# CONNECTORS.net
KiCad netlist of a schematic drawn in Altium Designer
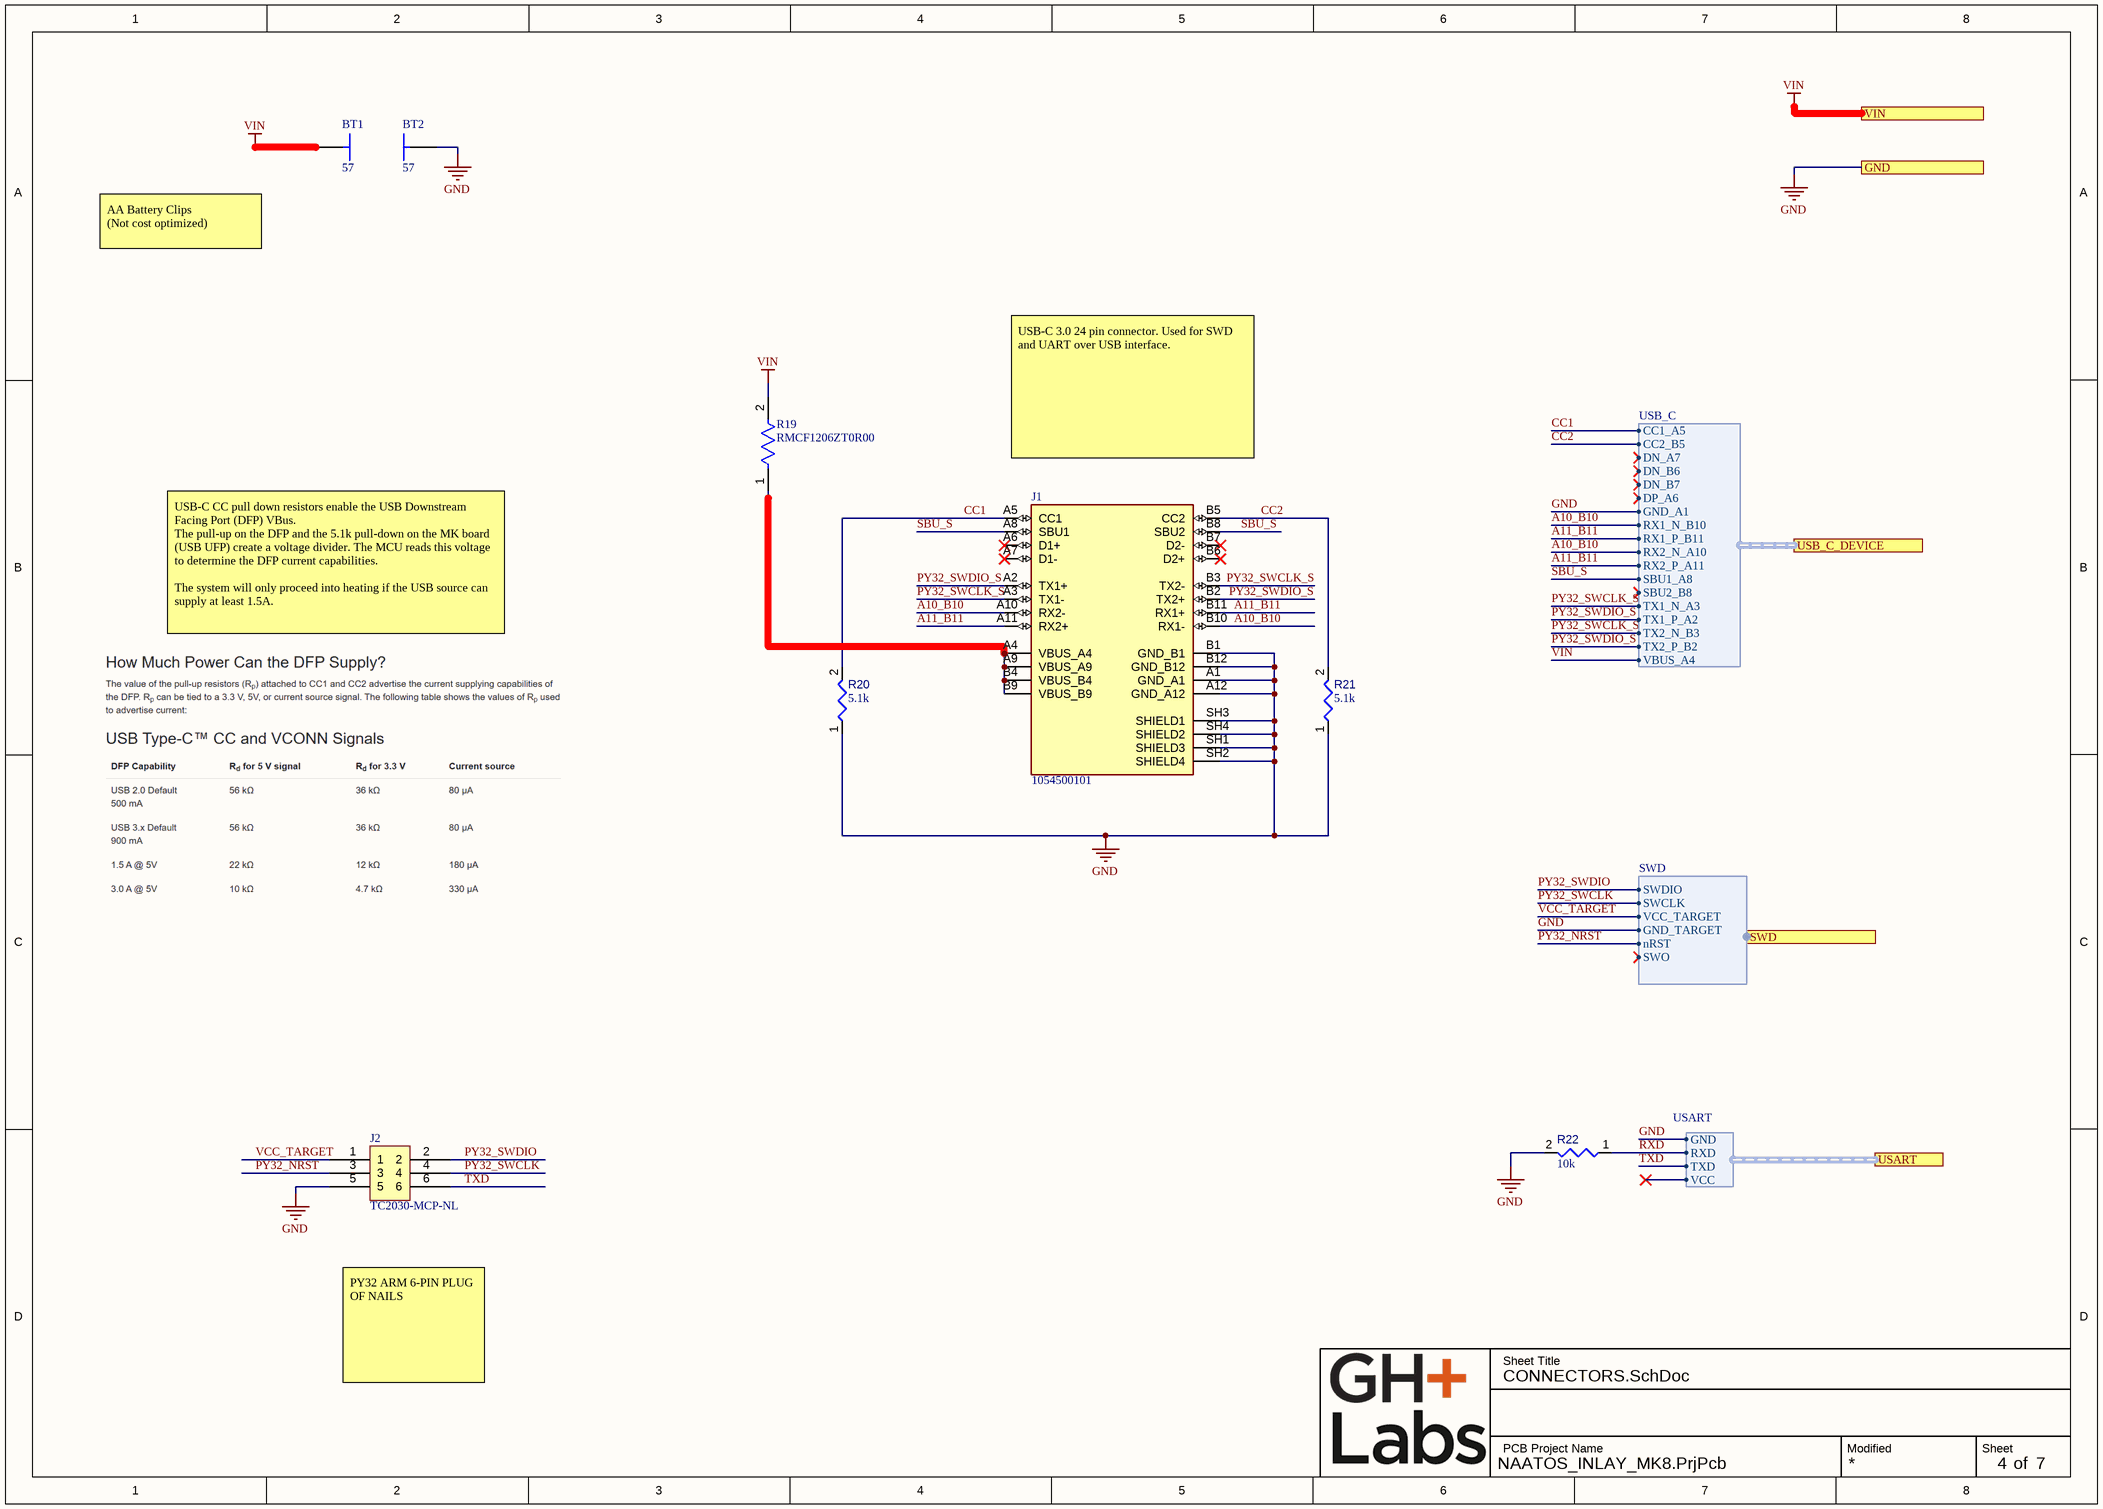
[diagram p0: CONNECTORS.SchDoc]

(export (version "E")
  (design (tool "Eeschema 10.0.6"))
  (components
    (comp (ref "BT1")
      (value "57")
      (footprint "57-Footprint-1")
      (description "A /AA SMT BATTERY CONTACT")
      (fields (field (name "MF") "Keystone Electronics"))
      (libsource (lib "Global Health Labs, Inc") (part "BT1"))
    )
    (comp (ref "BT2")
      (value "57")
      (footprint "57-Footprint-1")
      (description "A /AA SMT BATTERY CONTACT")
      (fields (field (name "MF") "Keystone Electronics"))
      (libsource (lib "Global Health Labs, Inc") (part "BT1"))
    )
    (comp (ref "J1")
      (value "1054500101")
      (footprint "MOLEX_1054500101")
      (fields (field (name "MF") "Molex"))
      (libsource (lib "Global Health Labs, Inc") (part "1054500101"))
    )
    (comp (ref "J2")
      (value "TC2030-MCP-NL")
      (footprint "TC2030-MCP-NL")
      (description "TAG CONNECT FOR UPDI")
      (libsource (lib "TC2030-MCP-NL") (part "TC2030-MCP-NL"))
    )
    (comp (ref "R19")
      (value "RMCF1206ZT0R00")
      (footprint "FP-RMCF1206-MFG")
      (description "0Ω ±0 0.25W 1206 Thick Film Chip Resistor AEC-Q200 compliant")
      (libsource (lib "Altium Content Vault") (part "1029c3af85768c4190bb7ad29bc67b5"))
    )
    (comp (ref "R20")
      (value "5.1k")
      (footprint "RESC0402(1005)_L")
      (description "Chip Resistor, 5.1 kOhms, +/-1 %, 63 mW, -55 to 155 degC, 0402")
      (fields (field (name "POWER") "63mW") (field (name "TOLERANCE") "1%"))
      (libsource (lib "Global Health Labs, Inc") (part "RES-2"))
    )
    (comp (ref "R21")
      (value "5.1k")
      (footprint "RESC0402(1005)_L")
      (description "Chip Resistor, 5.1 kOhms, +/-1 %, 63 mW, -55 to 155 degC, 0402")
      (fields (field (name "POWER") "63mW") (field (name "TOLERANCE") "1%"))
      (libsource (lib "Global Health Labs, Inc") (part "RES-2"))
    )
    (comp (ref "R22")
      (value "10k")
      (footprint "RESC0402(1005)_L")
      (description "Chip Resistor, 10 kOhms, +/-1 %, 63 mW, -55 to 125 degC, 0402")
      (fields (field (name "POWER") "63mW") (field (name "TOLERANCE") "1%"))
      (libsource (lib "Global Health Labs, Inc") (part "RES-2"))
    )
  )
  (nets
    (net (code "4") (name "/A10_B10") (class "Default")
      (node (ref "J1") (pin "A10") (pinfunction "RX2-_A10") (pintype "bidirectional"))
      (node (ref "J1") (pin "B10") (pinfunction "RX1-_B10") (pintype "bidirectional"))
    )
    (net (code "5") (name "/A11_B11") (class "Default")
      (node (ref "J1") (pin "A11") (pinfunction "RX2+_A11") (pintype "bidirectional"))
      (node (ref "J1") (pin "B11") (pinfunction "RX1+_B11") (pintype "bidirectional"))
    )
    (net (code "6") (name "/CC1") (class "Default")
      (node (ref "J1") (pin "A5") (pinfunction "CC1_A5") (pintype "bidirectional"))
      (node (ref "R20") (pin "2") (pinfunction "2_2") (pintype "passive"))
    )
    (net (code "7") (name "/CC2") (class "Default")
      (node (ref "J1") (pin "B5") (pinfunction "CC2_B5") (pintype "bidirectional"))
      (node (ref "R21") (pin "2") (pinfunction "2_2") (pintype "passive"))
    )
    (net (code "8") (name "/PY32_NRST") (class "Default")
      (node (ref "J2") (pin "3") (pinfunction "3_3") (pintype "passive"))
    )
    (net (code "9") (name "/PY32_SWCLK") (class "Default")
      (node (ref "J2") (pin "4") (pinfunction "4_4") (pintype "passive"))
    )
    (net (code "10") (name "/PY32_SWCLK_S") (class "Default")
      (node (ref "J1") (pin "A3") (pinfunction "TX1-_A3") (pintype "bidirectional"))
      (node (ref "J1") (pin "B3") (pinfunction "TX2-_B3") (pintype "bidirectional"))
    )
    (net (code "11") (name "/PY32_SWDIO") (class "Default")
      (node (ref "J2") (pin "2") (pinfunction "2_2") (pintype "passive"))
    )
    (net (code "12") (name "/PY32_SWDIO_S") (class "Default")
      (node (ref "J1") (pin "A2") (pinfunction "TX1+_A2") (pintype "bidirectional"))
      (node (ref "J1") (pin "B2") (pinfunction "TX2+_B2") (pintype "bidirectional"))
    )
    (net (code "13") (name "/RXD") (class "Default")
      (node (ref "R22") (pin "1") (pinfunction "1_1") (pintype "passive"))
    )
    (net (code "14") (name "/SBU_S") (class "Default")
      (node (ref "J1") (pin "A8") (pinfunction "SBU1_A8") (pintype "bidirectional"))
      (node (ref "J1") (pin "B8") (pinfunction "SBU2_B8") (pintype "bidirectional"))
    )
    (net (code "15") (name "/TXD") (class "Default")
      (node (ref "J2") (pin "6") (pinfunction "6_6") (pintype "passive"))
    )
    (net (code "16") (name "/VCC_TARGET") (class "Default")
      (node (ref "J2") (pin "1") (pinfunction "1_1") (pintype "passive"))
    )
    (net (code "20") (name "GND") (class "Default")
      (node (ref "BT2") (pin "P_1") (pinfunction "POS_P_1") (pintype "passive"))
      (node (ref "J1") (pin "A1") (pinfunction "GND_A1_A1") (pintype "power_in"))
      (node (ref "J1") (pin "A12") (pinfunction "GND_A12_A12") (pintype "power_in"))
      (node (ref "J1") (pin "B1") (pinfunction "GND_B1_B1") (pintype "power_in"))
      (node (ref "J1") (pin "B12") (pinfunction "GND_B12_B12") (pintype "power_in"))
      (node (ref "J1") (pin "SH1") (pinfunction "SHIELD3_SH1") (pintype "passive"))
      (node (ref "J1") (pin "SH2") (pinfunction "SHIELD4_SH2") (pintype "passive"))
      (node (ref "J1") (pin "SH3") (pinfunction "SHIELD1_SH3") (pintype "passive"))
      (node (ref "J1") (pin "SH4") (pinfunction "SHIELD2_SH4") (pintype "passive"))
      (node (ref "J2") (pin "5") (pinfunction "5_5") (pintype "passive"))
      (node (ref "R20") (pin "1") (pinfunction "1_1") (pintype "passive"))
      (node (ref "R21") (pin "1") (pinfunction "1_1") (pintype "passive"))
      (node (ref "R22") (pin "2") (pinfunction "2_2") (pintype "passive"))
    )
    (net (code "21") (name "Net-(J1-VBUS_A4)") (class "Default")
      (node (ref "J1") (pin "A4") (pinfunction "VBUS_A4_A4") (pintype "power_in"))
      (node (ref "J1") (pin "A9") (pinfunction "VBUS_A9_A9") (pintype "power_in"))
      (node (ref "J1") (pin "B4") (pinfunction "VBUS_B4_B4") (pintype "power_in"))
      (node (ref "J1") (pin "B9") (pinfunction "VBUS_B9_B9") (pintype "power_in"))
      (node (ref "R19") (pin "1") (pinfunction "1_1") (pintype "passive"))
    )
    (net (code "22") (name "VIN") (class "Default")
      (node (ref "BT1") (pin "P_1") (pinfunction "POS_P_1") (pintype "passive"))
      (node (ref "R19") (pin "2") (pinfunction "2_2") (pintype "passive"))
    )
    (net (code "23") (name "unconnected-(J1-D1+-PadA6)") (class "Default")
      (node (ref "J1") (pin "A6") (pinfunction "D1+_A6") (pintype "bidirectional+no_connect"))
    )
    (net (code "24") (name "unconnected-(J1-D1--PadA7)") (class "Default")
      (node (ref "J1") (pin "A7") (pinfunction "D1-_A7") (pintype "bidirectional+no_connect"))
    )
    (net (code "25") (name "unconnected-(J1-D2+-PadB6)") (class "Default")
      (node (ref "J1") (pin "B6") (pinfunction "D2+_B6") (pintype "bidirectional+no_connect"))
    )
    (net (code "26") (name "unconnected-(J1-D2--PadB7)") (class "Default")
      (node (ref "J1") (pin "B7") (pinfunction "D2-_B7") (pintype "bidirectional+no_connect"))
    )
  )
)
